# xen_daisy_motherboard_8cv8pt_mki.net
KiCad netlist of a schematic drawn in EAGLE
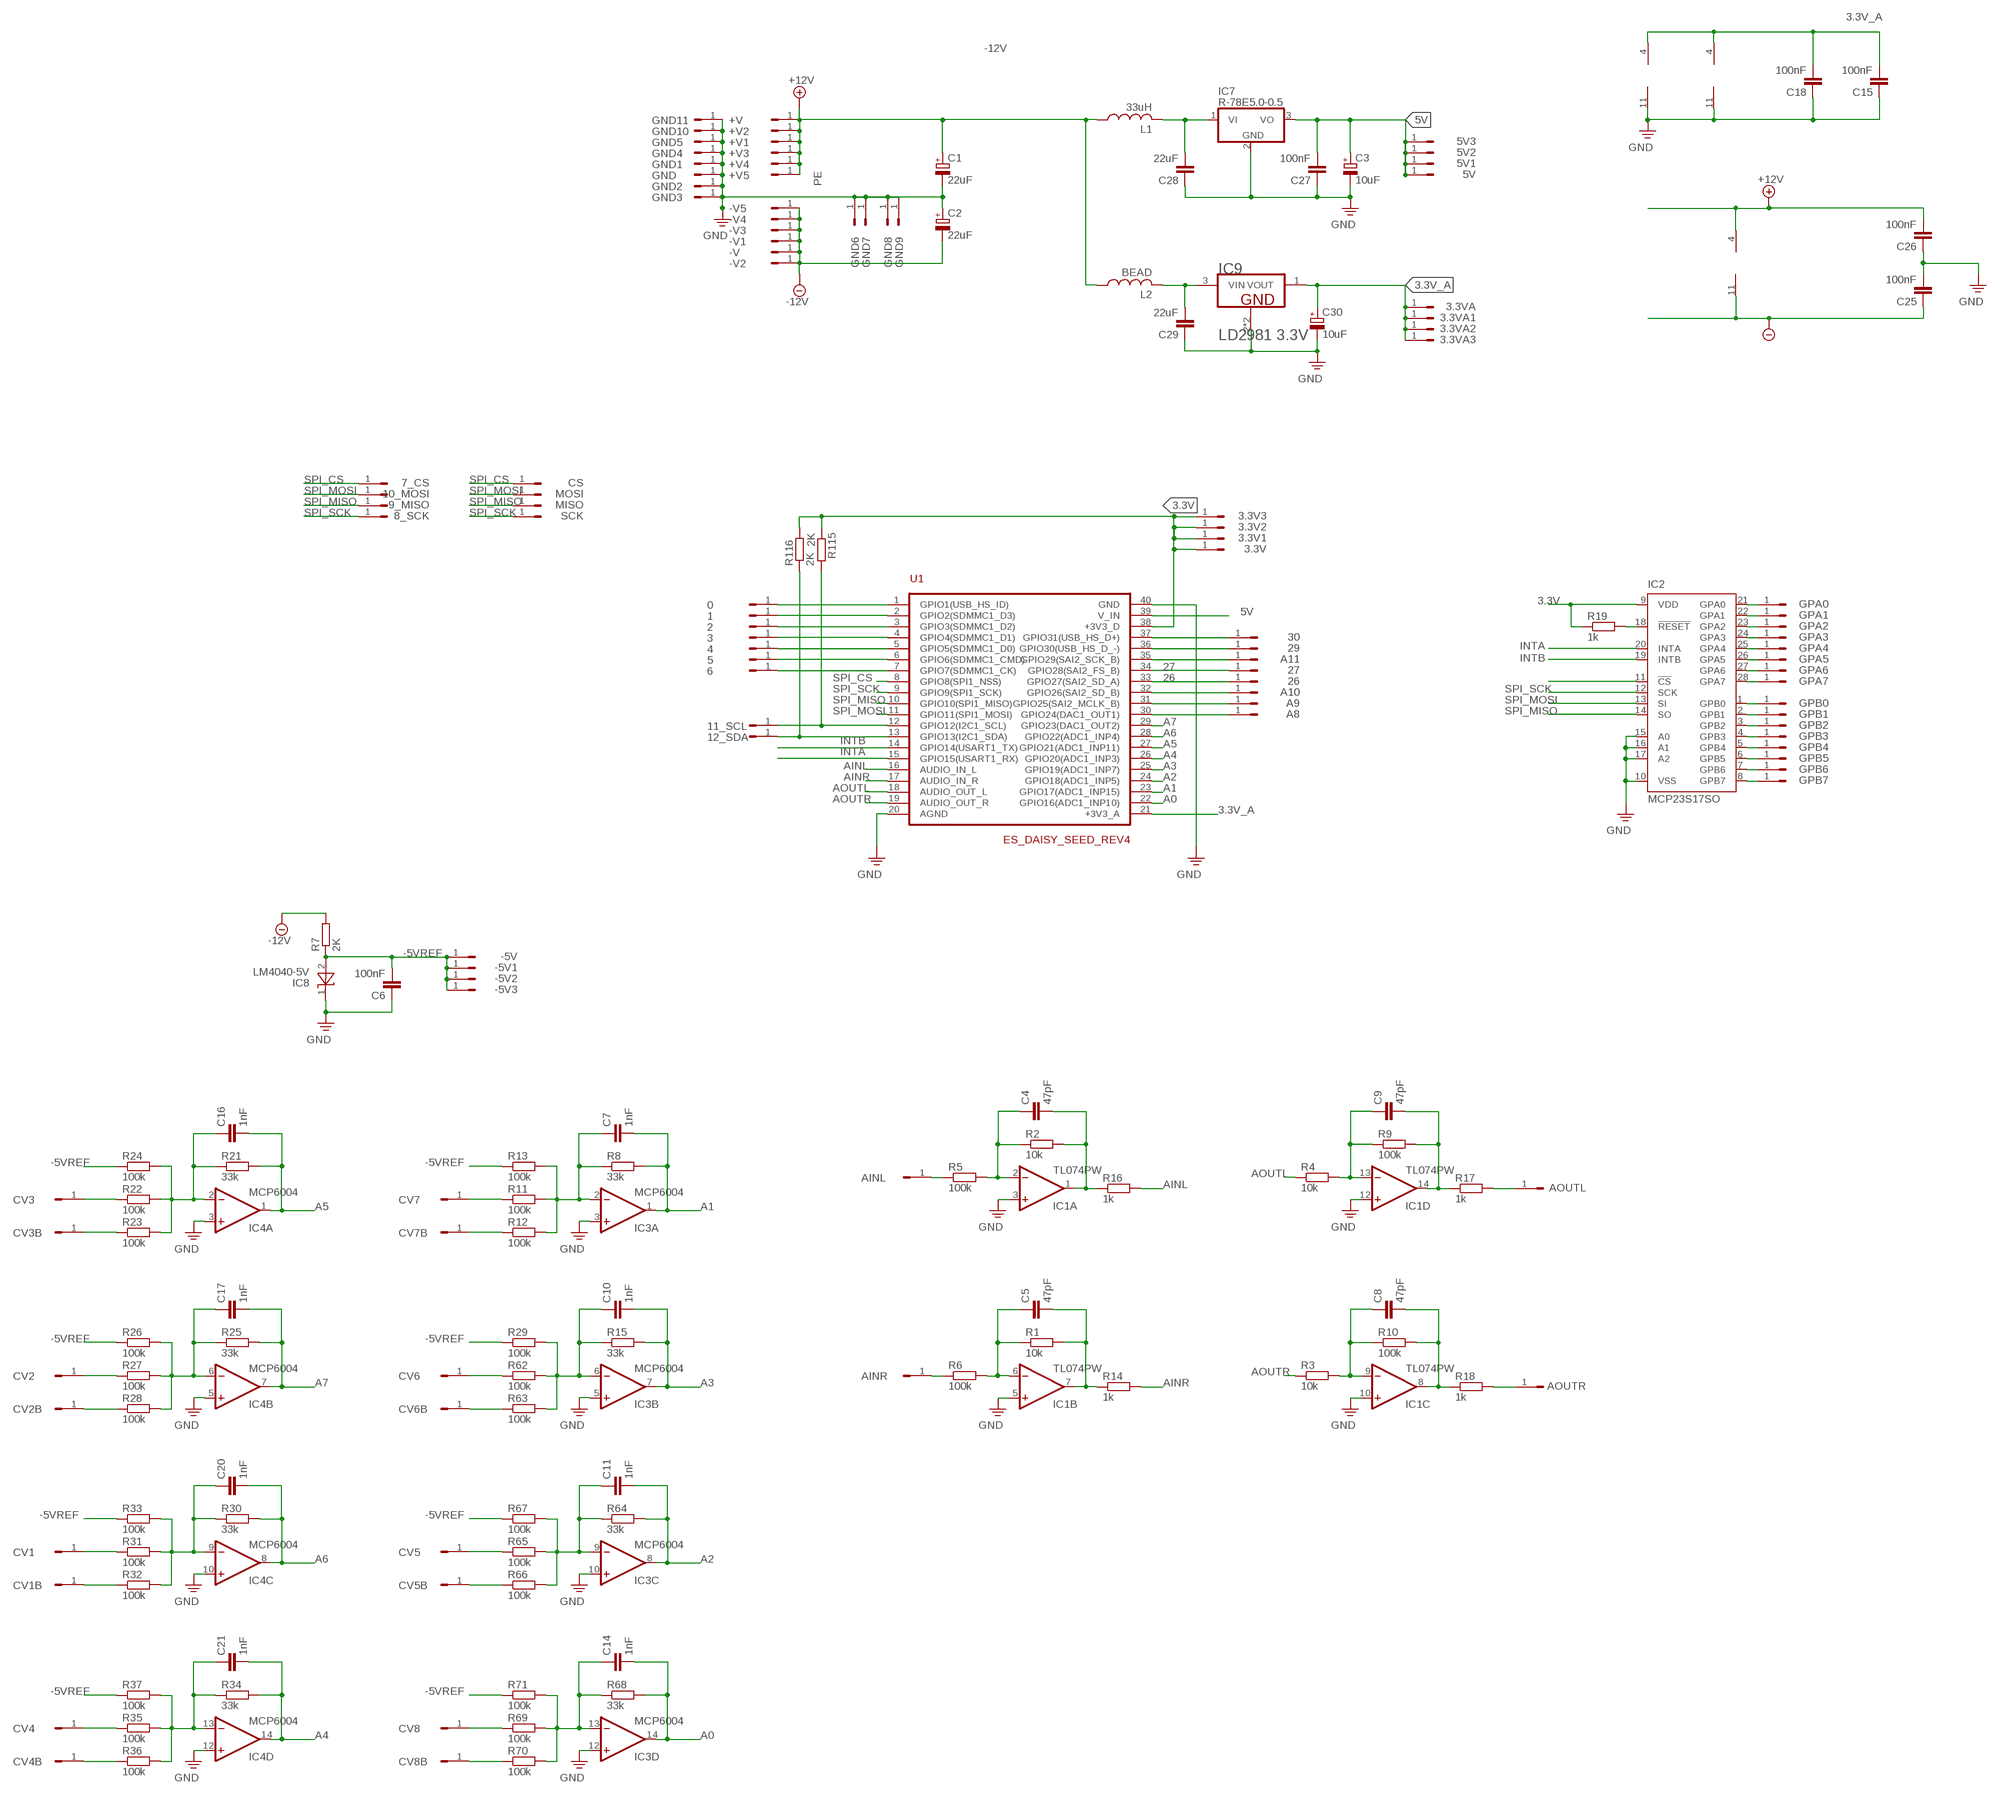
[diagram p0: schematic, sheet 1]

(export (version "E")
  (design (tool "Eeschema 10.0.6"))
  (components
    (comp (ref "+V")
      (value "HEADER/MALE/01")
      (footprint "eagle-import:HEADER_MALE_01")
      (fields (field (name "SPICEPREFIX") "X"))
      (libsource (lib "eagle-import") (part "HEADER/MALE/01"))
    )
    (comp (ref "+V1")
      (value "HEADER/MALE/01")
      (footprint "eagle-import:HEADER_MALE_01")
      (fields (field (name "SPICEPREFIX") "X"))
      (libsource (lib "eagle-import") (part "HEADER/MALE/01"))
    )
    (comp (ref "+V2")
      (value "HEADER/MALE/01")
      (footprint "eagle-import:HEADER_MALE_01")
      (fields (field (name "SPICEPREFIX") "X"))
      (libsource (lib "eagle-import") (part "HEADER/MALE/01"))
    )
    (comp (ref "+V3")
      (value "HEADER/MALE/01")
      (footprint "eagle-import:HEADER_MALE_01")
      (fields (field (name "SPICEPREFIX") "X"))
      (libsource (lib "eagle-import") (part "HEADER/MALE/01"))
    )
    (comp (ref "+V4")
      (value "HEADER/MALE/01")
      (footprint "eagle-import:HEADER_MALE_01")
      (fields (field (name "SPICEPREFIX") "X"))
      (libsource (lib "eagle-import") (part "HEADER/MALE/01"))
    )
    (comp (ref "+V5")
      (value "HEADER/MALE/01")
      (footprint "eagle-import:HEADER_MALE_01")
      (fields (field (name "SPICEPREFIX") "X"))
      (libsource (lib "eagle-import") (part "HEADER/MALE/01"))
    )
    (comp (ref "-5V")
      (value "HEADER/MALE/01")
      (footprint "eagle-import:HEADER_MALE_01")
      (fields (field (name "SPICEPREFIX") "X"))
      (libsource (lib "eagle-import") (part "HEADER/MALE/01"))
    )
    (comp (ref "-5V1")
      (value "HEADER/MALE/01")
      (footprint "eagle-import:HEADER_MALE_01")
      (fields (field (name "SPICEPREFIX") "X"))
      (libsource (lib "eagle-import") (part "HEADER/MALE/01"))
    )
    (comp (ref "-5V2")
      (value "HEADER/MALE/01")
      (footprint "eagle-import:HEADER_MALE_01")
      (fields (field (name "SPICEPREFIX") "X"))
      (libsource (lib "eagle-import") (part "HEADER/MALE/01"))
    )
    (comp (ref "-5V3")
      (value "HEADER/MALE/01")
      (footprint "eagle-import:HEADER_MALE_01")
      (fields (field (name "SPICEPREFIX") "X"))
      (libsource (lib "eagle-import") (part "HEADER/MALE/01"))
    )
    (comp (ref "-V")
      (value "HEADER/MALE/01")
      (footprint "eagle-import:HEADER_MALE_01")
      (fields (field (name "SPICEPREFIX") "X"))
      (libsource (lib "eagle-import") (part "HEADER/MALE/01"))
    )
    (comp (ref "-V1")
      (value "HEADER/MALE/01")
      (footprint "eagle-import:HEADER_MALE_01")
      (fields (field (name "SPICEPREFIX") "X"))
      (libsource (lib "eagle-import") (part "HEADER/MALE/01"))
    )
    (comp (ref "-V2")
      (value "HEADER/MALE/01")
      (footprint "eagle-import:HEADER_MALE_01")
      (fields (field (name "SPICEPREFIX") "X"))
      (libsource (lib "eagle-import") (part "HEADER/MALE/01"))
    )
    (comp (ref "-V3")
      (value "HEADER/MALE/01")
      (footprint "eagle-import:HEADER_MALE_01")
      (fields (field (name "SPICEPREFIX") "X"))
      (libsource (lib "eagle-import") (part "HEADER/MALE/01"))
    )
    (comp (ref "-V4")
      (value "HEADER/MALE/01")
      (footprint "eagle-import:HEADER_MALE_01")
      (fields (field (name "SPICEPREFIX") "X"))
      (libsource (lib "eagle-import") (part "HEADER/MALE/01"))
    )
    (comp (ref "-V5")
      (value "HEADER/MALE/01")
      (footprint "eagle-import:HEADER_MALE_01")
      (fields (field (name "SPICEPREFIX") "X"))
      (libsource (lib "eagle-import") (part "HEADER/MALE/01"))
    )
    (comp (ref "0")
      (value "HEADER/MALE/01")
      (footprint "eagle-import:HEADER_MALE_01")
      (fields (field (name "SPICEPREFIX") "X"))
      (libsource (lib "eagle-import") (part "HEADER/MALE/01"))
    )
    (comp (ref "1")
      (value "HEADER/MALE/01")
      (footprint "eagle-import:HEADER_MALE_01")
      (fields (field (name "SPICEPREFIX") "X"))
      (libsource (lib "eagle-import") (part "HEADER/MALE/01"))
    )
    (comp (ref "2")
      (value "HEADER/MALE/01")
      (footprint "eagle-import:HEADER_MALE_01")
      (fields (field (name "SPICEPREFIX") "X"))
      (libsource (lib "eagle-import") (part "HEADER/MALE/01"))
    )
    (comp (ref "3")
      (value "HEADER/MALE/01")
      (footprint "eagle-import:HEADER_MALE_01")
      (fields (field (name "SPICEPREFIX") "X"))
      (libsource (lib "eagle-import") (part "HEADER/MALE/01"))
    )
    (comp (ref "3.3V")
      (value "HEADER/MALE/01")
      (footprint "eagle-import:HEADER_MALE_01")
      (fields (field (name "SPICEPREFIX") "X"))
      (libsource (lib "eagle-import") (part "HEADER/MALE/01"))
    )
    (comp (ref "3.3V1")
      (value "HEADER/MALE/01")
      (footprint "eagle-import:HEADER_MALE_01")
      (fields (field (name "SPICEPREFIX") "X"))
      (libsource (lib "eagle-import") (part "HEADER/MALE/01"))
    )
    (comp (ref "3.3V2")
      (value "HEADER/MALE/01")
      (footprint "eagle-import:HEADER_MALE_01")
      (fields (field (name "SPICEPREFIX") "X"))
      (libsource (lib "eagle-import") (part "HEADER/MALE/01"))
    )
    (comp (ref "3.3V3")
      (value "HEADER/MALE/01")
      (footprint "eagle-import:HEADER_MALE_01")
      (fields (field (name "SPICEPREFIX") "X"))
      (libsource (lib "eagle-import") (part "HEADER/MALE/01"))
    )
    (comp (ref "3.3VA")
      (value "HEADER/MALE/01")
      (footprint "eagle-import:HEADER_MALE_01")
      (fields (field (name "SPICEPREFIX") "X"))
      (libsource (lib "eagle-import") (part "HEADER/MALE/01"))
    )
    (comp (ref "3.3VA1")
      (value "HEADER/MALE/01")
      (footprint "eagle-import:HEADER_MALE_01")
      (fields (field (name "SPICEPREFIX") "X"))
      (libsource (lib "eagle-import") (part "HEADER/MALE/01"))
    )
    (comp (ref "3.3VA2")
      (value "HEADER/MALE/01")
      (footprint "eagle-import:HEADER_MALE_01")
      (fields (field (name "SPICEPREFIX") "X"))
      (libsource (lib "eagle-import") (part "HEADER/MALE/01"))
    )
    (comp (ref "3.3VA3")
      (value "HEADER/MALE/01")
      (footprint "eagle-import:HEADER_MALE_01")
      (fields (field (name "SPICEPREFIX") "X"))
      (libsource (lib "eagle-import") (part "HEADER/MALE/01"))
    )
    (comp (ref "4")
      (value "HEADER/MALE/01")
      (footprint "eagle-import:HEADER_MALE_01")
      (fields (field (name "SPICEPREFIX") "X"))
      (libsource (lib "eagle-import") (part "HEADER/MALE/01"))
    )
    (comp (ref "5")
      (value "HEADER/MALE/01")
      (footprint "eagle-import:HEADER_MALE_01")
      (fields (field (name "SPICEPREFIX") "X"))
      (libsource (lib "eagle-import") (part "HEADER/MALE/01"))
    )
    (comp (ref "5V")
      (value "HEADER/MALE/01")
      (footprint "eagle-import:HEADER_MALE_01")
      (fields (field (name "SPICEPREFIX") "X"))
      (libsource (lib "eagle-import") (part "HEADER/MALE/01"))
    )
    (comp (ref "5V1")
      (value "HEADER/MALE/01")
      (footprint "eagle-import:HEADER_MALE_01")
      (fields (field (name "SPICEPREFIX") "X"))
      (libsource (lib "eagle-import") (part "HEADER/MALE/01"))
    )
    (comp (ref "5V2")
      (value "HEADER/MALE/01")
      (footprint "eagle-import:HEADER_MALE_01")
      (fields (field (name "SPICEPREFIX") "X"))
      (libsource (lib "eagle-import") (part "HEADER/MALE/01"))
    )
    (comp (ref "5V3")
      (value "HEADER/MALE/01")
      (footprint "eagle-import:HEADER_MALE_01")
      (fields (field (name "SPICEPREFIX") "X"))
      (libsource (lib "eagle-import") (part "HEADER/MALE/01"))
    )
    (comp (ref "6")
      (value "HEADER/MALE/01")
      (footprint "eagle-import:HEADER_MALE_01")
      (fields (field (name "SPICEPREFIX") "X"))
      (libsource (lib "eagle-import") (part "HEADER/MALE/01"))
    )
    (comp (ref "7_CS")
      (value "HEADER/MALE/01")
      (footprint "eagle-import:HEADER_MALE_01")
      (fields (field (name "SPICEPREFIX") "X"))
      (libsource (lib "eagle-import") (part "HEADER/MALE/01"))
    )
    (comp (ref "8_SCK")
      (value "HEADER/MALE/01")
      (footprint "eagle-import:HEADER_MALE_01")
      (fields (field (name "SPICEPREFIX") "X"))
      (libsource (lib "eagle-import") (part "HEADER/MALE/01"))
    )
    (comp (ref "9_MISO")
      (value "HEADER/MALE/01")
      (footprint "eagle-import:HEADER_MALE_01")
      (fields (field (name "SPICEPREFIX") "X"))
      (libsource (lib "eagle-import") (part "HEADER/MALE/01"))
    )
    (comp (ref "10_MOSI")
      (value "HEADER/MALE/01")
      (footprint "eagle-import:HEADER_MALE_01")
      (fields (field (name "SPICEPREFIX") "X"))
      (libsource (lib "eagle-import") (part "HEADER/MALE/01"))
    )
    (comp (ref "11_SCL")
      (value "HEADER/MALE/01")
      (footprint "eagle-import:HEADER_MALE_01")
      (fields (field (name "SPICEPREFIX") "X"))
      (libsource (lib "eagle-import") (part "HEADER/MALE/01"))
    )
    (comp (ref "12_SDA")
      (value "HEADER/MALE/01")
      (footprint "eagle-import:HEADER_MALE_01")
      (fields (field (name "SPICEPREFIX") "X"))
      (libsource (lib "eagle-import") (part "HEADER/MALE/01"))
    )
    (comp (ref "26")
      (value "HEADER/MALE/01")
      (footprint "eagle-import:HEADER_MALE_01")
      (fields (field (name "SPICEPREFIX") "X"))
      (libsource (lib "eagle-import") (part "HEADER/MALE/01"))
    )
    (comp (ref "27")
      (value "HEADER/MALE/01")
      (footprint "eagle-import:HEADER_MALE_01")
      (fields (field (name "SPICEPREFIX") "X"))
      (libsource (lib "eagle-import") (part "HEADER/MALE/01"))
    )
    (comp (ref "29")
      (value "HEADER/MALE/01")
      (footprint "eagle-import:HEADER_MALE_01")
      (fields (field (name "SPICEPREFIX") "X"))
      (libsource (lib "eagle-import") (part "HEADER/MALE/01"))
    )
    (comp (ref "30")
      (value "HEADER/MALE/01")
      (footprint "eagle-import:HEADER_MALE_01")
      (fields (field (name "SPICEPREFIX") "X"))
      (libsource (lib "eagle-import") (part "HEADER/MALE/01"))
    )
    (comp (ref "A8")
      (value "HEADER/MALE/01")
      (footprint "eagle-import:HEADER_MALE_01")
      (fields (field (name "SPICEPREFIX") "X"))
      (libsource (lib "eagle-import") (part "HEADER/MALE/01"))
    )
    (comp (ref "A9")
      (value "HEADER/MALE/01")
      (footprint "eagle-import:HEADER_MALE_01")
      (fields (field (name "SPICEPREFIX") "X"))
      (libsource (lib "eagle-import") (part "HEADER/MALE/01"))
    )
    (comp (ref "A10")
      (value "HEADER/MALE/01")
      (footprint "eagle-import:HEADER_MALE_01")
      (fields (field (name "SPICEPREFIX") "X"))
      (libsource (lib "eagle-import") (part "HEADER/MALE/01"))
    )
    (comp (ref "A11")
      (value "HEADER/MALE/01")
      (footprint "eagle-import:HEADER_MALE_01")
      (fields (field (name "SPICEPREFIX") "X"))
      (libsource (lib "eagle-import") (part "HEADER/MALE/01"))
    )
    (comp (ref "AINL")
      (value "HEADER/MALE/01")
      (footprint "eagle-import:HEADER_MALE_01")
      (fields (field (name "SPICEPREFIX") "X"))
      (libsource (lib "eagle-import") (part "HEADER/MALE/01"))
    )
    (comp (ref "AINR")
      (value "HEADER/MALE/01")
      (footprint "eagle-import:HEADER_MALE_01")
      (fields (field (name "SPICEPREFIX") "X"))
      (libsource (lib "eagle-import") (part "HEADER/MALE/01"))
    )
    (comp (ref "AOUTL")
      (value "HEADER/MALE/01")
      (footprint "eagle-import:HEADER_MALE_01")
      (fields (field (name "SPICEPREFIX") "X"))
      (libsource (lib "eagle-import") (part "HEADER/MALE/01"))
    )
    (comp (ref "AOUTR")
      (value "HEADER/MALE/01")
      (footprint "eagle-import:HEADER_MALE_01")
      (fields (field (name "SPICEPREFIX") "X"))
      (libsource (lib "eagle-import") (part "HEADER/MALE/01"))
    )
    (comp (ref "C1")
      (value "22uF")
      (footprint "eagle-import:SV-C")
      (fields (field (name "SPICEPREFIX") "C"))
      (libsource (lib "eagle-import") (part "CAPACITOR/POLARIZEDSMDC"))
    )
    (comp (ref "C2")
      (value "22uF")
      (footprint "eagle-import:SV-C")
      (fields (field (name "SPICEPREFIX") "C"))
      (libsource (lib "eagle-import") (part "CAPACITOR/POLARIZEDSMDC"))
    )
    (comp (ref "C3")
      (value "10uF")
      (footprint "eagle-import:SV-B")
      (fields (field (name "SPICEPREFIX") "C"))
      (libsource (lib "eagle-import") (part "CAPACITOR/POLARIZEDSMDB"))
    )
    (comp (ref "C4")
      (value "47pF")
      (footprint "eagle-import:C0603")
      (libsource (lib "eagle-import") (part "CAPACITORC0603"))
    )
    (comp (ref "C5")
      (value "47pF")
      (footprint "eagle-import:C0603")
      (libsource (lib "eagle-import") (part "CAPACITORC0603"))
    )
    (comp (ref "C6")
      (value "100nF")
      (footprint "eagle-import:C0603")
      (libsource (lib "eagle-import") (part "CAPACITORC0603"))
    )
    (comp (ref "C7")
      (value "1nF")
      (footprint "eagle-import:C0603")
      (libsource (lib "eagle-import") (part "CAPACITORC0603"))
    )
    (comp (ref "C8")
      (value "47pF")
      (footprint "eagle-import:C0603")
      (libsource (lib "eagle-import") (part "CAPACITORC0603"))
    )
    (comp (ref "C9")
      (value "47pF")
      (footprint "eagle-import:C0603")
      (libsource (lib "eagle-import") (part "CAPACITORC0603"))
    )
    (comp (ref "C10")
      (value "1nF")
      (footprint "eagle-import:C0603")
      (libsource (lib "eagle-import") (part "CAPACITORC0603"))
    )
    (comp (ref "C11")
      (value "1nF")
      (footprint "eagle-import:C0603")
      (libsource (lib "eagle-import") (part "CAPACITORC0603"))
    )
    (comp (ref "C14")
      (value "1nF")
      (footprint "eagle-import:C0603")
      (libsource (lib "eagle-import") (part "CAPACITORC0603"))
    )
    (comp (ref "C15")
      (value "100nF")
      (footprint "eagle-import:C0603")
      (fields (field (name "SPICEPREFIX") "C"))
      (libsource (lib "eagle-import") (part "CAPACITORC0603"))
    )
    (comp (ref "C16")
      (value "1nF")
      (footprint "eagle-import:C0603")
      (libsource (lib "eagle-import") (part "CAPACITORC0603"))
    )
    (comp (ref "C17")
      (value "1nF")
      (footprint "eagle-import:C0603")
      (libsource (lib "eagle-import") (part "CAPACITORC0603"))
    )
    (comp (ref "C18")
      (value "100nF")
      (footprint "eagle-import:C0603")
      (fields (field (name "SPICEPREFIX") "C"))
      (libsource (lib "eagle-import") (part "CAPACITORC0603"))
    )
    (comp (ref "C20")
      (value "1nF")
      (footprint "eagle-import:C0603")
      (libsource (lib "eagle-import") (part "CAPACITORC0603"))
    )
    (comp (ref "C21")
      (value "1nF")
      (footprint "eagle-import:C0603")
      (libsource (lib "eagle-import") (part "CAPACITORC0603"))
    )
    (comp (ref "C25")
      (value "100nF")
      (footprint "eagle-import:C0603")
      (fields (field (name "SPICEPREFIX") "C"))
      (libsource (lib "eagle-import") (part "CAPACITORC0603"))
    )
    (comp (ref "C26")
      (value "100nF")
      (footprint "eagle-import:C0603")
      (fields (field (name "SPICEPREFIX") "C"))
      (libsource (lib "eagle-import") (part "CAPACITORC0603"))
    )
    (comp (ref "C27")
      (value "100nF")
      (footprint "eagle-import:C0603")
      (libsource (lib "eagle-import") (part "CAPACITORC0603"))
    )
    (comp (ref "C28")
      (value "22uF")
      (footprint "eagle-import:C0805")
      (libsource (lib "eagle-import") (part "CAPACITORC0805"))
    )
    (comp (ref "C29")
      (value "22uF")
      (footprint "eagle-import:C0805")
      (libsource (lib "eagle-import") (part "CAPACITORC0805"))
    )
    (comp (ref "C30")
      (value "10uF")
      (footprint "eagle-import:SV-B")
      (fields (field (name "SPICEPREFIX") "C"))
      (libsource (lib "eagle-import") (part "CAPACITOR/POLARIZEDSMDB"))
    )
    (comp (ref "CS")
      (value "HEADER/MALE/01")
      (footprint "eagle-import:HEADER_MALE_01")
      (fields (field (name "SPICEPREFIX") "X"))
      (libsource (lib "eagle-import") (part "HEADER/MALE/01"))
    )
    (comp (ref "CV1")
      (value "HEADER/MALE/01")
      (footprint "eagle-import:HEADER_MALE_01")
      (fields (field (name "SPICEPREFIX") "X"))
      (libsource (lib "eagle-import") (part "HEADER/MALE/01"))
    )
    (comp (ref "CV1B")
      (value "HEADER/MALE/01")
      (footprint "eagle-import:HEADER_MALE_01")
      (fields (field (name "SPICEPREFIX") "X"))
      (libsource (lib "eagle-import") (part "HEADER/MALE/01"))
    )
    (comp (ref "CV2")
      (value "HEADER/MALE/01")
      (footprint "eagle-import:HEADER_MALE_01")
      (fields (field (name "SPICEPREFIX") "X"))
      (libsource (lib "eagle-import") (part "HEADER/MALE/01"))
    )
    (comp (ref "CV2B")
      (value "HEADER/MALE/01")
      (footprint "eagle-import:HEADER_MALE_01")
      (fields (field (name "SPICEPREFIX") "X"))
      (libsource (lib "eagle-import") (part "HEADER/MALE/01"))
    )
    (comp (ref "CV3")
      (value "HEADER/MALE/01")
      (footprint "eagle-import:HEADER_MALE_01")
      (fields (field (name "SPICEPREFIX") "X"))
      (libsource (lib "eagle-import") (part "HEADER/MALE/01"))
    )
    (comp (ref "CV3B")
      (value "HEADER/MALE/01")
      (footprint "eagle-import:HEADER_MALE_01")
      (fields (field (name "SPICEPREFIX") "X"))
      (libsource (lib "eagle-import") (part "HEADER/MALE/01"))
    )
    (comp (ref "CV4")
      (value "HEADER/MALE/01")
      (footprint "eagle-import:HEADER_MALE_01")
      (fields (field (name "SPICEPREFIX") "X"))
      (libsource (lib "eagle-import") (part "HEADER/MALE/01"))
    )
    (comp (ref "CV4B")
      (value "HEADER/MALE/01")
      (footprint "eagle-import:HEADER_MALE_01")
      (fields (field (name "SPICEPREFIX") "X"))
      (libsource (lib "eagle-import") (part "HEADER/MALE/01"))
    )
    (comp (ref "CV5")
      (value "HEADER/MALE/01")
      (footprint "eagle-import:HEADER_MALE_01")
      (fields (field (name "SPICEPREFIX") "X"))
      (libsource (lib "eagle-import") (part "HEADER/MALE/01"))
    )
    (comp (ref "CV5B")
      (value "HEADER/MALE/01")
      (footprint "eagle-import:HEADER_MALE_01")
      (fields (field (name "SPICEPREFIX") "X"))
      (libsource (lib "eagle-import") (part "HEADER/MALE/01"))
    )
    (comp (ref "CV6")
      (value "HEADER/MALE/01")
      (footprint "eagle-import:HEADER_MALE_01")
      (fields (field (name "SPICEPREFIX") "X"))
      (libsource (lib "eagle-import") (part "HEADER/MALE/01"))
    )
    (comp (ref "CV6B")
      (value "HEADER/MALE/01")
      (footprint "eagle-import:HEADER_MALE_01")
      (fields (field (name "SPICEPREFIX") "X"))
      (libsource (lib "eagle-import") (part "HEADER/MALE/01"))
    )
    (comp (ref "CV7")
      (value "HEADER/MALE/01")
      (footprint "eagle-import:HEADER_MALE_01")
      (fields (field (name "SPICEPREFIX") "X"))
      (libsource (lib "eagle-import") (part "HEADER/MALE/01"))
    )
    (comp (ref "CV7B")
      (value "HEADER/MALE/01")
      (footprint "eagle-import:HEADER_MALE_01")
      (fields (field (name "SPICEPREFIX") "X"))
      (libsource (lib "eagle-import") (part "HEADER/MALE/01"))
    )
    (comp (ref "CV8")
      (value "HEADER/MALE/01")
      (footprint "eagle-import:HEADER_MALE_01")
      (fields (field (name "SPICEPREFIX") "X"))
      (libsource (lib "eagle-import") (part "HEADER/MALE/01"))
    )
    (comp (ref "CV8B")
      (value "HEADER/MALE/01")
      (footprint "eagle-import:HEADER_MALE_01")
      (fields (field (name "SPICEPREFIX") "X"))
      (libsource (lib "eagle-import") (part "HEADER/MALE/01"))
    )
    (comp (ref "GND")
      (value "HEADER/MALE/01")
      (footprint "eagle-import:HEADER_MALE_01")
      (fields (field (name "SPICEPREFIX") "X"))
      (libsource (lib "eagle-import") (part "HEADER/MALE/01"))
    )
    (comp (ref "GND1")
      (value "HEADER/MALE/01")
      (footprint "eagle-import:HEADER_MALE_01")
      (fields (field (name "SPICEPREFIX") "X"))
      (libsource (lib "eagle-import") (part "HEADER/MALE/01"))
    )
    (comp (ref "GND2")
      (value "HEADER/MALE/01")
      (footprint "eagle-import:HEADER_MALE_01")
      (fields (field (name "SPICEPREFIX") "X"))
      (libsource (lib "eagle-import") (part "HEADER/MALE/01"))
    )
    (comp (ref "GND3")
      (value "HEADER/MALE/01")
      (footprint "eagle-import:HEADER_MALE_01")
      (fields (field (name "SPICEPREFIX") "X"))
      (libsource (lib "eagle-import") (part "HEADER/MALE/01"))
    )
    (comp (ref "GND4")
      (value "HEADER/MALE/01")
      (footprint "eagle-import:HEADER_MALE_01")
      (fields (field (name "SPICEPREFIX") "X"))
      (libsource (lib "eagle-import") (part "HEADER/MALE/01"))
    )
    (comp (ref "GND5")
      (value "HEADER/MALE/01")
      (footprint "eagle-import:HEADER_MALE_01")
      (fields (field (name "SPICEPREFIX") "X"))
      (libsource (lib "eagle-import") (part "HEADER/MALE/01"))
    )
    (comp (ref "GND6")
      (value "HEADER/MALE/01")
      (footprint "eagle-import:HEADER_MALE_01")
      (fields (field (name "SPICEPREFIX") "X"))
      (libsource (lib "eagle-import") (part "HEADER/MALE/01"))
    )
    (comp (ref "GND7")
      (value "HEADER/MALE/01")
      (footprint "eagle-import:HEADER_MALE_01")
      (fields (field (name "SPICEPREFIX") "X"))
      (libsource (lib "eagle-import") (part "HEADER/MALE/01"))
    )
    (comp (ref "GND8")
      (value "HEADER/MALE/01")
      (footprint "eagle-import:HEADER_MALE_01")
      (fields (field (name "SPICEPREFIX") "X"))
      (libsource (lib "eagle-import") (part "HEADER/MALE/01"))
    )
    (comp (ref "GND9")
      (value "HEADER/MALE/01")
      (footprint "eagle-import:HEADER_MALE_01")
      (fields (field (name "SPICEPREFIX") "X"))
      (libsource (lib "eagle-import") (part "HEADER/MALE/01"))
    )
    (comp (ref "GND10")
      (value "HEADER/MALE/01")
      (footprint "eagle-import:HEADER_MALE_01")
      (fields (field (name "SPICEPREFIX") "X"))
      (libsource (lib "eagle-import") (part "HEADER/MALE/01"))
    )
    (comp (ref "GND11")
      (value "HEADER/MALE/01")
      (footprint "eagle-import:HEADER_MALE_01")
      (fields (field (name "SPICEPREFIX") "X"))
      (libsource (lib "eagle-import") (part "HEADER/MALE/01"))
    )
    (comp (ref "GPA0")
      (value "HEADER/MALE/01")
      (footprint "eagle-import:HEADER_MALE_01")
      (fields (field (name "SPICEPREFIX") "X"))
      (libsource (lib "eagle-import") (part "HEADER/MALE/01"))
    )
    (comp (ref "GPA1")
      (value "HEADER/MALE/01")
      (footprint "eagle-import:HEADER_MALE_01")
      (fields (field (name "SPICEPREFIX") "X"))
      (libsource (lib "eagle-import") (part "HEADER/MALE/01"))
    )
    (comp (ref "GPA2")
      (value "HEADER/MALE/01")
      (footprint "eagle-import:HEADER_MALE_01")
      (fields (field (name "SPICEPREFIX") "X"))
      (libsource (lib "eagle-import") (part "HEADER/MALE/01"))
    )
    (comp (ref "GPA3")
      (value "HEADER/MALE/01")
      (footprint "eagle-import:HEADER_MALE_01")
      (fields (field (name "SPICEPREFIX") "X"))
      (libsource (lib "eagle-import") (part "HEADER/MALE/01"))
    )
    (comp (ref "GPA4")
      (value "HEADER/MALE/01")
      (footprint "eagle-import:HEADER_MALE_01")
      (fields (field (name "SPICEPREFIX") "X"))
      (libsource (lib "eagle-import") (part "HEADER/MALE/01"))
    )
    (comp (ref "GPA5")
      (value "HEADER/MALE/01")
      (footprint "eagle-import:HEADER_MALE_01")
      (fields (field (name "SPICEPREFIX") "X"))
      (libsource (lib "eagle-import") (part "HEADER/MALE/01"))
    )
    (comp (ref "GPA6")
      (value "HEADER/MALE/01")
      (footprint "eagle-import:HEADER_MALE_01")
      (fields (field (name "SPICEPREFIX") "X"))
      (libsource (lib "eagle-import") (part "HEADER/MALE/01"))
    )
    (comp (ref "GPA7")
      (value "HEADER/MALE/01")
      (footprint "eagle-import:HEADER_MALE_01")
      (fields (field (name "SPICEPREFIX") "X"))
      (libsource (lib "eagle-import") (part "HEADER/MALE/01"))
    )
    (comp (ref "GPB0")
      (value "HEADER/MALE/01")
      (footprint "eagle-import:HEADER_MALE_01")
      (fields (field (name "SPICEPREFIX") "X"))
      (libsource (lib "eagle-import") (part "HEADER/MALE/01"))
    )
    (comp (ref "GPB1")
      (value "HEADER/MALE/01")
      (footprint "eagle-import:HEADER_MALE_01")
      (fields (field (name "SPICEPREFIX") "X"))
      (libsource (lib "eagle-import") (part "HEADER/MALE/01"))
    )
    (comp (ref "GPB2")
      (value "HEADER/MALE/01")
      (footprint "eagle-import:HEADER_MALE_01")
      (fields (field (name "SPICEPREFIX") "X"))
      (libsource (lib "eagle-import") (part "HEADER/MALE/01"))
    )
    (comp (ref "GPB3")
      (value "HEADER/MALE/01")
      (footprint "eagle-import:HEADER_MALE_01")
      (fields (field (name "SPICEPREFIX") "X"))
      (libsource (lib "eagle-import") (part "HEADER/MALE/01"))
    )
    (comp (ref "GPB4")
      (value "HEADER/MALE/01")
      (footprint "eagle-import:HEADER_MALE_01")
      (fields (field (name "SPICEPREFIX") "X"))
      (libsource (lib "eagle-import") (part "HEADER/MALE/01"))
    )
    (comp (ref "GPB5")
      (value "HEADER/MALE/01")
      (footprint "eagle-import:HEADER_MALE_01")
      (fields (field (name "SPICEPREFIX") "X"))
      (libsource (lib "eagle-import") (part "HEADER/MALE/01"))
    )
    (comp (ref "GPB6")
      (value "HEADER/MALE/01")
      (footprint "eagle-import:HEADER_MALE_01")
      (fields (field (name "SPICEPREFIX") "X"))
      (libsource (lib "eagle-import") (part "HEADER/MALE/01"))
    )
    (comp (ref "GPB7")
      (value "HEADER/MALE/01")
      (footprint "eagle-import:HEADER_MALE_01")
      (fields (field (name "SPICEPREFIX") "X"))
      (libsource (lib "eagle-import") (part "HEADER/MALE/01"))
    )
    (comp (ref "IC1")
      (value "TL074PW")
      (footprint "eagle-import:TSSOP14")
      (fields (field (name "SPICEPREFIX") "I"))
      (libsource (lib "eagle-import") (part "TL074PW"))
    )
    (comp (ref "IC2")
      (value "MCP23S17SO")
      (footprint "eagle-import:SO28W")
      (fields (field (name "MF") "MICROCHIP") (field (name "MPN") "MCP23S17-E/SO"))
      (libsource (lib "eagle-import") (part "MCP23S17SO"))
    )
    (comp (ref "IC3")
      (value "MCP6004")
      (footprint "eagle-import:TSSOP14")
      (fields (field (name "SPICEPREFIX") "I"))
      (libsource (lib "eagle-import") (part "TL074PW"))
    )
    (comp (ref "IC4")
      (value "MCP6004")
      (footprint "eagle-import:TSSOP14")
      (fields (field (name "SPICEPREFIX") "I"))
      (libsource (lib "eagle-import") (part "TL074PW"))
    )
    (comp (ref "IC7")
      (value "R-78E5.0-0.5")
      (footprint "eagle-import:WE78")
      (libsource (lib "eagle-import") (part "WE173950378"))
    )
    (comp (ref "IC8")
      (value "LM4040-5V")
      (footprint "eagle-import:SOT-23")
      (libsource (lib "eagle-import") (part "LM4040CYM3-2.5"))
    )
    (comp (ref "IC9")
      (value "LD2981 3.3V")
      (footprint "eagle-import:LD2981-SOT89")
      (fields (field (name "MF") "STMicroelectronics") (field (name "MPN") "LD2981CU33TR"))
      (libsource (lib "eagle-import") (part "LD2981LD2981-SOT89"))
    )
    (comp (ref "L1")
      (value "33uH")
      (footprint "eagle-import:L2012C")
      (libsource (lib "eagle-import") (part "INDUCTORL2012C"))
    )
    (comp (ref "L2")
      (value "BEAD")
      (footprint "eagle-import:R0603")
      (libsource (lib "eagle-import") (part "INDUCTORL0603"))
    )
    (comp (ref "MISO")
      (value "HEADER/MALE/01")
      (footprint "eagle-import:HEADER_MALE_01")
      (fields (field (name "SPICEPREFIX") "X"))
      (libsource (lib "eagle-import") (part "HEADER/MALE/01"))
    )
    (comp (ref "MOSI")
      (value "HEADER/MALE/01")
      (footprint "eagle-import:HEADER_MALE_01")
      (fields (field (name "SPICEPREFIX") "X"))
      (libsource (lib "eagle-import") (part "HEADER/MALE/01"))
    )
    (comp (ref "R1")
      (value "10k")
      (footprint "eagle-import:R0603")
      (libsource (lib "eagle-import") (part "RESISTOR"))
    )
    (comp (ref "R2")
      (value "10k")
      (footprint "eagle-import:R0603")
      (libsource (lib "eagle-import") (part "RESISTOR"))
    )
    (comp (ref "R3")
      (value "10k")
      (footprint "eagle-import:R0603")
      (libsource (lib "eagle-import") (part "RESISTOR"))
    )
    (comp (ref "R4")
      (value "10k")
      (footprint "eagle-import:R0603")
      (libsource (lib "eagle-import") (part "RESISTOR"))
    )
    (comp (ref "R5")
      (value "100k")
      (footprint "eagle-import:R0603")
      (libsource (lib "eagle-import") (part "RESISTOR"))
    )
    (comp (ref "R6")
      (value "100k")
      (footprint "eagle-import:R0603")
      (libsource (lib "eagle-import") (part "RESISTOR"))
    )
    (comp (ref "R7")
      (value "2K")
      (footprint "eagle-import:R0603")
      (libsource (lib "eagle-import") (part "RESISTOR"))
    )
    (comp (ref "R8")
      (value "33k")
      (footprint "eagle-import:R0603")
      (libsource (lib "eagle-import") (part "RESISTOR"))
    )
    (comp (ref "R9")
      (value "100k")
      (footprint "eagle-import:R0603")
      (libsource (lib "eagle-import") (part "RESISTOR"))
    )
    (comp (ref "R10")
      (value "100k")
      (footprint "eagle-import:R0603")
      (libsource (lib "eagle-import") (part "RESISTOR"))
    )
    (comp (ref "R11")
      (value "100k")
      (footprint "eagle-import:R0603")
      (libsource (lib "eagle-import") (part "RESISTOR"))
    )
    (comp (ref "R12")
      (value "100k")
      (footprint "eagle-import:R0603")
      (libsource (lib "eagle-import") (part "RESISTOR"))
    )
    (comp (ref "R13")
      (value "100k")
      (footprint "eagle-import:R0603")
      (libsource (lib "eagle-import") (part "RESISTOR"))
    )
    (comp (ref "R14")
      (value "1k")
      (footprint "eagle-import:R0603")
      (libsource (lib "eagle-import") (part "RESISTOR"))
    )
    (comp (ref "R15")
      (value "33k")
      (footprint "eagle-import:R0603")
      (libsource (lib "eagle-import") (part "RESISTOR"))
    )
    (comp (ref "R16")
      (value "1k")
      (footprint "eagle-import:R0603")
      (libsource (lib "eagle-import") (part "RESISTOR"))
    )
    (comp (ref "R17")
      (value "1k")
      (footprint "eagle-import:R0603")
      (libsource (lib "eagle-import") (part "RESISTOR"))
    )
    (comp (ref "R18")
      (value "1k")
      (footprint "eagle-import:R0603")
      (libsource (lib "eagle-import") (part "RESISTOR"))
    )
    (comp (ref "R19")
      (value "1k")
      (footprint "eagle-import:R0603")
      (libsource (lib "eagle-import") (part "RESISTOR"))
    )
    (comp (ref "R21")
      (value "33k")
      (footprint "eagle-import:R0603")
      (libsource (lib "eagle-import") (part "RESISTOR"))
    )
    (comp (ref "R22")
      (value "100k")
      (footprint "eagle-import:R0603")
      (libsource (lib "eagle-import") (part "RESISTOR"))
    )
    (comp (ref "R23")
      (value "100k")
      (footprint "eagle-import:R0603")
      (libsource (lib "eagle-import") (part "RESISTOR"))
    )
    (comp (ref "R24")
      (value "100k")
      (footprint "eagle-import:R0603")
      (libsource (lib "eagle-import") (part "RESISTOR"))
    )
    (comp (ref "R25")
      (value "33k")
      (footprint "eagle-import:R0603")
      (libsource (lib "eagle-import") (part "RESISTOR"))
    )
    (comp (ref "R26")
      (value "100k")
      (footprint "eagle-import:R0603")
      (libsource (lib "eagle-import") (part "RESISTOR"))
    )
    (comp (ref "R27")
      (value "100k")
      (footprint "eagle-import:R0603")
      (libsource (lib "eagle-import") (part "RESISTOR"))
    )
    (comp (ref "R28")
      (value "100k")
      (footprint "eagle-import:R0603")
      (libsource (lib "eagle-import") (part "RESISTOR"))
    )
    (comp (ref "R29")
      (value "100k")
      (footprint "eagle-import:R0603")
      (libsource (lib "eagle-import") (part "RESISTOR"))
    )
    (comp (ref "R30")
      (value "33k")
      (footprint "eagle-import:R0603")
      (libsource (lib "eagle-import") (part "RESISTOR"))
    )
    (comp (ref "R31")
      (value "100k")
      (footprint "eagle-import:R0603")
      (libsource (lib "eagle-import") (part "RESISTOR"))
    )
    (comp (ref "R32")
      (value "100k")
      (footprint "eagle-import:R0603")
      (libsource (lib "eagle-import") (part "RESISTOR"))
    )
    (comp (ref "R33")
      (value "100k")
      (footprint "eagle-import:R0603")
      (libsource (lib "eagle-import") (part "RESISTOR"))
    )
    (comp (ref "R34")
      (value "33k")
      (footprint "eagle-import:R0603")
      (libsource (lib "eagle-import") (part "RESISTOR"))
    )
    (comp (ref "R35")
      (value "100k")
      (footprint "eagle-import:R0603")
      (libsource (lib "eagle-import") (part "RESISTOR"))
    )
    (comp (ref "R36")
      (value "100k")
      (footprint "eagle-import:R0603")
      (libsource (lib "eagle-import") (part "RESISTOR"))
    )
    (comp (ref "R37")
      (value "100k")
      (footprint "eagle-import:R0603")
      (libsource (lib "eagle-import") (part "RESISTOR"))
    )
    (comp (ref "R62")
      (value "100k")
      (footprint "eagle-import:R0603")
      (libsource (lib "eagle-import") (part "RESISTOR"))
    )
    (comp (ref "R63")
      (value "100k")
      (footprint "eagle-import:R0603")
      (libsource (lib "eagle-import") (part "RESISTOR"))
    )
    (comp (ref "R64")
      (value "33k")
      (footprint "eagle-import:R0603")
      (libsource (lib "eagle-import") (part "RESISTOR"))
    )
    (comp (ref "R65")
      (value "100k")
      (footprint "eagle-import:R0603")
      (libsource (lib "eagle-import") (part "RESISTOR"))
    )
    (comp (ref "R66")
      (value "100k")
      (footprint "eagle-import:R0603")
      (libsource (lib "eagle-import") (part "RESISTOR"))
    )
    (comp (ref "R67")
      (value "100k")
      (footprint "eagle-import:R0603")
      (libsource (lib "eagle-import") (part "RESISTOR"))
    )
    (comp (ref "R68")
      (value "33k")
      (footprint "eagle-import:R0603")
      (libsource (lib "eagle-import") (part "RESISTOR"))
    )
    (comp (ref "R69")
      (value "100k")
      (footprint "eagle-import:R0603")
      (libsource (lib "eagle-import") (part "RESISTOR"))
    )
    (comp (ref "R70")
      (value "100k")
      (footprint "eagle-import:R0603")
      (libsource (lib "eagle-import") (part "RESISTOR"))
    )
    (comp (ref "R71")
      (value "100k")
      (footprint "eagle-import:R0603")
      (libsource (lib "eagle-import") (part "RESISTOR"))
    )
    (comp (ref "R115")
      (value "2K")
      (footprint "eagle-import:R0603")
      (libsource (lib "eagle-import") (part "RESISTOR"))
    )
    (comp (ref "R116")
      (value "2K")
      (footprint "eagle-import:R0603")
      (libsource (lib "eagle-import") (part "RESISTOR"))
    )
    (comp (ref "SCK")
      (value "HEADER/MALE/01")
      (footprint "eagle-import:HEADER_MALE_01")
      (fields (field (name "SPICEPREFIX") "X"))
      (libsource (lib "eagle-import") (part "HEADER/MALE/01"))
    )
    (comp (ref "U1")
      (value "ES_DAISY_SEED_REV4")
      (footprint "eagle-import:ES_DAISY_SEED")
      (libsource (lib "eagle-import") (part "ES_DAISY_SEED_REV4"))
    )
  )
  (nets
    (net (code "1") (name "+12V") (class "Default")
      (node (ref "+V") (pin "1") (pinfunction "3_1") (pintype "passive"))
      (node (ref "+V1") (pin "1") (pinfunction "3_1") (pintype "passive"))
      (node (ref "+V2") (pin "1") (pinfunction "3_1") (pintype "passive"))
      (node (ref "+V3") (pin "1") (pinfunction "3_1") (pintype "passive"))
      (node (ref "+V4") (pin "1") (pinfunction "3_1") (pintype "passive"))
      (node (ref "+V5") (pin "1") (pinfunction "3_1") (pintype "passive"))
      (node (ref "C1") (pin "+") (pinfunction "+_+") (pintype "passive"))
      (node (ref "C26") (pin "2") (pinfunction "2_2") (pintype "passive"))
      (node (ref "IC1") (pin "4") (pinfunction "V+_4") (pintype "power_in"))
      (node (ref "L1") (pin "1") (pinfunction "1_1") (pintype "passive"))
      (node (ref "L2") (pin "1") (pinfunction "1_1") (pintype "passive"))
    )
    (net (code "2") (name "-12V") (class "Default")
      (node (ref "-V") (pin "1") (pinfunction "3_1") (pintype "passive"))
      (node (ref "-V1") (pin "1") (pinfunction "3_1") (pintype "passive"))
      (node (ref "-V2") (pin "1") (pinfunction "3_1") (pintype "passive"))
      (node (ref "-V3") (pin "1") (pinfunction "3_1") (pintype "passive"))
      (node (ref "-V4") (pin "1") (pinfunction "3_1") (pintype "passive"))
      (node (ref "-V5") (pin "1") (pinfunction "3_1") (pintype "passive"))
      (node (ref "C2") (pin "-") (pinfunction "-_-") (pintype "passive"))
      (node (ref "C25") (pin "1") (pinfunction "1_1") (pintype "passive"))
      (node (ref "IC1") (pin "11") (pinfunction "V-_11") (pintype "power_in"))
      (node (ref "R7") (pin "2") (pinfunction "2_2") (pintype "passive"))
    )
    (net (code "3") (name "/-5VREF") (class "Default")
      (node (ref "-5V") (pin "1") (pinfunction "3_1") (pintype "passive"))
      (node (ref "-5V1") (pin "1") (pinfunction "3_1") (pintype "passive"))
      (node (ref "-5V2") (pin "1") (pinfunction "3_1") (pintype "passive"))
      (node (ref "-5V3") (pin "1") (pinfunction "3_1") (pintype "passive"))
      (node (ref "C6") (pin "2") (pinfunction "2_2") (pintype "passive"))
      (node (ref "IC8") (pin "2") (pinfunction "A_2") (pintype "output"))
      (node (ref "R13") (pin "1") (pinfunction "1_1") (pintype "passive"))
      (node (ref "R24") (pin "1") (pinfunction "1_1") (pintype "passive"))
      (node (ref "R26") (pin "1") (pinfunction "1_1") (pintype "passive"))
      (node (ref "R29") (pin "1") (pinfunction "1_1") (pintype "passive"))
      (node (ref "R33") (pin "1") (pinfunction "1_1") (pintype "passive"))
      (node (ref "R37") (pin "1") (pinfunction "1_1") (pintype "passive"))
      (node (ref "R67") (pin "1") (pinfunction "1_1") (pintype "passive"))
      (node (ref "R7") (pin "1") (pinfunction "1_1") (pintype "passive"))
      (node (ref "R71") (pin "1") (pinfunction "1_1") (pintype "passive"))
    )
    (net (code "4") (name "/26") (class "Default")
      (node (ref "26") (pin "1") (pinfunction "3_1") (pintype "passive"))
      (node (ref "U1") (pin "33") (pinfunction "GPIO27(SAI2_SD_A)_33") (pintype "bidirectional"))
    )
    (net (code "5") (name "/27") (class "Default")
      (node (ref "27") (pin "1") (pinfunction "3_1") (pintype "passive"))
      (node (ref "U1") (pin "34") (pinfunction "GPIO28(SAI2_FS_B)_34") (pintype "bidirectional"))
    )
    (net (code "6") (name "/A0") (class "Default")
      (node (ref "C14") (pin "2") (pinfunction "2_2") (pintype "passive"))
      (node (ref "IC3") (pin "14") (pinfunction "OUT_14") (pintype "output"))
      (node (ref "R68") (pin "2") (pinfunction "2_2") (pintype "passive"))
      (node (ref "U1") (pin "22") (pinfunction "GPIO16(ADC1_INP10)_22") (pintype "bidirectional"))
    )
    (net (code "7") (name "/A1") (class "Default")
      (node (ref "C7") (pin "2") (pinfunction "2_2") (pintype "passive"))
      (node (ref "IC3") (pin "1") (pinfunction "OUT_1") (pintype "output"))
      (node (ref "R8") (pin "2") (pinfunction "2_2") (pintype "passive"))
      (node (ref "U1") (pin "23") (pinfunction "GPIO17(ADC1_INP15)_23") (pintype "bidirectional"))
    )
    (net (code "8") (name "/A2") (class "Default")
      (node (ref "C11") (pin "2") (pinfunction "2_2") (pintype "passive"))
      (node (ref "IC3") (pin "8") (pinfunction "OUT_8") (pintype "output"))
      (node (ref "R64") (pin "2") (pinfunction "2_2") (pintype "passive"))
      (node (ref "U1") (pin "24") (pinfunction "GPIO18(ADC1_INP5)_24") (pintype "bidirectional"))
    )
    (net (code "9") (name "/A3") (class "Default")
      (node (ref "C10") (pin "2") (pinfunction "2_2") (pintype "passive"))
      (node (ref "IC3") (pin "7") (pinfunction "OUT_7") (pintype "output"))
      (node (ref "R15") (pin "2") (pinfunction "2_2") (pintype "passive"))
      (node (ref "U1") (pin "25") (pinfunction "GPIO19(ADC1_INP7)_25") (pintype "bidirectional"))
    )
    (net (code "10") (name "/A4") (class "Default")
      (node (ref "C21") (pin "2") (pinfunction "2_2") (pintype "passive"))
      (node (ref "IC4") (pin "14") (pinfunction "OUT_14") (pintype "output"))
      (node (ref "R34") (pin "2") (pinfunction "2_2") (pintype "passive"))
      (node (ref "U1") (pin "26") (pinfunction "GPIO20(ADC1_INP3)_26") (pintype "bidirectional"))
    )
    (net (code "11") (name "/A5") (class "Default")
      (node (ref "C16") (pin "2") (pinfunction "2_2") (pintype "passive"))
      (node (ref "IC4") (pin "1") (pinfunction "OUT_1") (pintype "output"))
      (node (ref "R21") (pin "2") (pinfunction "2_2") (pintype "passive"))
      (node (ref "U1") (pin "27") (pinfunction "GPIO21(ADC1_INP11)_27") (pintype "bidirectional"))
    )
    (net (code "12") (name "/A6") (class "Default")
      (node (ref "C20") (pin "2") (pinfunction "2_2") (pintype "passive"))
      (node (ref "IC4") (pin "8") (pinfunction "OUT_8") (pintype "output"))
      (node (ref "R30") (pin "2") (pinfunction "2_2") (pintype "passive"))
      (node (ref "U1") (pin "28") (pinfunction "GPIO22(ADC1_INP4)_28") (pintype "bidirectional"))
    )
    (net (code "13") (name "/A7") (class "Default")
      (node (ref "C17") (pin "2") (pinfunction "2_2") (pintype "passive"))
      (node (ref "IC4") (pin "7") (pinfunction "OUT_7") (pintype "output"))
      (node (ref "R25") (pin "2") (pinfunction "2_2") (pintype "passive"))
      (node (ref "U1") (pin "29") (pinfunction "GPIO23(DAC1_OUT2)_29") (pintype "bidirectional"))
    )
    (net (code "14") (name "/AINL") (class "Default")
      (node (ref "R16") (pin "2") (pinfunction "2_2") (pintype "passive"))
      (node (ref "U1") (pin "16") (pinfunction "AUDIO_IN_L_16") (pintype "bidirectional"))
    )
    (net (code "15") (name "/AINR") (class "Default")
      (node (ref "R14") (pin "2") (pinfunction "2_2") (pintype "passive"))
      (node (ref "U1") (pin "17") (pinfunction "AUDIO_IN_R_17") (pintype "bidirectional"))
    )
    (net (code "16") (name "/AOUTL") (class "Default")
      (node (ref "R4") (pin "1") (pinfunction "1_1") (pintype "passive"))
      (node (ref "U1") (pin "18") (pinfunction "AUDIO_OUT_L_18") (pintype "bidirectional"))
    )
    (net (code "17") (name "/AOUTR") (class "Default")
      (node (ref "R3") (pin "1") (pinfunction "1_1") (pintype "passive"))
      (node (ref "U1") (pin "19") (pinfunction "AUDIO_OUT_R_19") (pintype "bidirectional"))
    )
    (net (code "18") (name "/INTA") (class "Default")
      (node (ref "IC2") (pin "20") (pinfunction "INTA_20") (pintype "output"))
      (node (ref "U1") (pin "15") (pinfunction "GPIO15(USART1_RX)_15") (pintype "bidirectional"))
    )
    (net (code "19") (name "/INTB") (class "Default")
      (node (ref "IC2") (pin "19") (pinfunction "INTB_19") (pintype "output"))
      (node (ref "U1") (pin "14") (pinfunction "GPIO14(USART1_TX)_14") (pintype "bidirectional"))
    )
    (net (code "20") (name "/SPI_CS") (class "Default")
      (node (ref "7_CS") (pin "1") (pinfunction "3_1") (pintype "passive"))
      (node (ref "CS") (pin "1") (pinfunction "3_1") (pintype "passive"))
      (node (ref "U1") (pin "8") (pinfunction "GPIO8(SPI1_NSS)_8") (pintype "bidirectional"))
    )
    (net (code "21") (name "/SPI_MISO") (class "Default")
      (node (ref "9_MISO") (pin "1") (pinfunction "3_1") (pintype "passive"))
      (node (ref "IC2") (pin "14") (pinfunction "SO_14") (pintype "output"))
      (node (ref "MISO") (pin "1") (pinfunction "3_1") (pintype "passive"))
      (node (ref "U1") (pin "10") (pinfunction "GPIO10(SPI1_MISO)_10") (pintype "bidirectional"))
    )
    (net (code "22") (name "/SPI_MOSI") (class "Default")
      (node (ref "10_MOSI") (pin "1") (pinfunction "3_1") (pintype "passive"))
      (node (ref "IC2") (pin "13") (pinfunction "SI_13") (pintype "input"))
      (node (ref "MOSI") (pin "1") (pinfunction "3_1") (pintype "passive"))
      (node (ref "U1") (pin "11") (pinfunction "GPIO11(SPI1_MOSI)_11") (pintype "bidirectional"))
    )
    (net (code "23") (name "/SPI_SCK") (class "Default")
      (node (ref "8_SCK") (pin "1") (pinfunction "3_1") (pintype "passive"))
      (node (ref "IC2") (pin "12") (pinfunction "SCK_12") (pintype "input"))
      (node (ref "SCK") (pin "1") (pinfunction "3_1") (pintype "passive"))
      (node (ref "U1") (pin "9") (pinfunction "GPIO9(SPI1_SCK)_9") (pintype "bidirectional"))
    )
    (net (code "24") (name "3.3V") (class "Default")
      (node (ref "3.3V") (pin "1") (pinfunction "3_1") (pintype "passive"))
      (node (ref "3.3V1") (pin "1") (pinfunction "3_1") (pintype "passive"))
      (node (ref "3.3V2") (pin "1") (pinfunction "3_1") (pintype "passive"))
      (node (ref "3.3V3") (pin "1") (pinfunction "3_1") (pintype "passive"))
      (node (ref "IC2") (pin "9") (pinfunction "VDD_9") (pintype "power_in"))
      (node (ref "R115") (pin "1") (pinfunction "1_1") (pintype "passive"))
      (node (ref "R116") (pin "2") (pinfunction "2_2") (pintype "passive"))
      (node (ref "R19") (pin "1") (pinfunction "1_1") (pintype "passive"))
      (node (ref "U1") (pin "38") (pinfunction "+3V3_D_38") (pintype "bidirectional"))
    )
    (net (code "25") (name "3.3V_A") (class "Default")
      (node (ref "3.3VA") (pin "1") (pinfunction "3_1") (pintype "passive"))
      (node (ref "3.3VA1") (pin "1") (pinfunction "3_1") (pintype "passive"))
      (node (ref "3.3VA2") (pin "1") (pinfunction "3_1") (pintype "passive"))
      (node (ref "3.3VA3") (pin "1") (pinfunction "3_1") (pintype "passive"))
      (node (ref "C15") (pin "2") (pinfunction "2_2") (pintype "passive"))
      (node (ref "C18") (pin "2") (pinfunction "2_2") (pintype "passive"))
      (node (ref "C30") (pin "+") (pinfunction "+_+") (pintype "passive"))
      (node (ref "IC3") (pin "4") (pinfunction "V+_4") (pintype "power_in"))
      (node (ref "IC4") (pin "4") (pinfunction "V+_4") (pintype "power_in"))
      (node (ref "IC9") (pin "1") (pinfunction "VOUT_1") (pintype "power_in"))
      (node (ref "U1") (pin "21") (pinfunction "+3V3_A_21") (pintype "bidirectional"))
    )
    (net (code "26") (name "5V") (class "Default")
      (node (ref "5V") (pin "1") (pinfunction "3_1") (pintype "passive"))
      (node (ref "5V1") (pin "1") (pinfunction "3_1") (pintype "passive"))
      (node (ref "5V2") (pin "1") (pinfunction "3_1") (pintype "passive"))
      (node (ref "5V3") (pin "1") (pinfunction "3_1") (pintype "passive"))
      (node (ref "C27") (pin "2") (pinfunction "2_2") (pintype "passive"))
      (node (ref "C3") (pin "+") (pinfunction "+_+") (pintype "passive"))
      (node (ref "IC7") (pin "3") (pinfunction "VO_3") (pintype "passive"))
      (node (ref "U1") (pin "39") (pinfunction "V_IN_39") (pintype "bidirectional"))
    )
    (net (code "27") (name "GND") (class "Default")
      (node (ref "C1") (pin "-") (pinfunction "-_-") (pintype "passive"))
      (node (ref "C15") (pin "1") (pinfunction "1_1") (pintype "passive"))
      (node (ref "C18") (pin "1") (pinfunction "1_1") (pintype "passive"))
      (node (ref "C2") (pin "+") (pinfunction "+_+") (pintype "passive"))
      (node (ref "C25") (pin "2") (pinfunction "2_2") (pintype "passive"))
      (node (ref "C26") (pin "1") (pinfunction "1_1") (pintype "passive"))
      (node (ref "C27") (pin "1") (pinfunction "1_1") (pintype "passive"))
      (node (ref "C28") (pin "1") (pinfunction "1_1") (pintype "passive"))
      (node (ref "C29") (pin "1") (pinfunction "1_1") (pintype "passive"))
      (node (ref "C3") (pin "-") (pinfunction "-_-") (pintype "passive"))
      (node (ref "C30") (pin "-") (pinfunction "-_-") (pintype "passive"))
      (node (ref "C6") (pin "1") (pinfunction "1_1") (pintype "passive"))
      (node (ref "GND") (pin "1") (pinfunction "3_1") (pintype "passive"))
      (node (ref "GND1") (pin "1") (pinfunction "3_1") (pintype "passive"))
      (node (ref "GND10") (pin "1") (pinfunction "3_1") (pintype "passive"))
      (node (ref "GND11") (pin "1") (pinfunction "3_1") (pintype "passive"))
      (node (ref "GND2") (pin "1") (pinfunction "3_1") (pintype "passive"))
      (node (ref "GND3") (pin "1") (pinfunction "3_1") (pintype "passive"))
      (node (ref "GND4") (pin "1") (pinfunction "3_1") (pintype "passive"))
      (node (ref "GND5") (pin "1") (pinfunction "3_1") (pintype "passive"))
      (node (ref "GND6") (pin "1") (pinfunction "3_1") (pintype "passive"))
      (node (ref "GND7") (pin "1") (pinfunction "3_1") (pintype "passive"))
      (node (ref "GND8") (pin "1") (pinfunction "3_1") (pintype "passive"))
      (node (ref "GND9") (pin "1") (pinfunction "3_1") (pintype "passive"))
      (node (ref "IC1") (pin "10") (pinfunction "+IN_10") (pintype "input"))
      (node (ref "IC1") (pin "12") (pinfunction "+IN_12") (pintype "input"))
      (node (ref "IC1") (pin "3") (pinfunction "+IN_3") (pintype "input"))
      (node (ref "IC1") (pin "5") (pinfunction "+IN_5") (pintype "input"))
      (node (ref "IC2") (pin "10") (pinfunction "VSS_10") (pintype "power_in"))
      (node (ref "IC2") (pin "15") (pinfunction "A0_15") (pintype "input"))
      (node (ref "IC2") (pin "16") (pinfunction "A1_16") (pintype "input"))
      (node (ref "IC2") (pin "17") (pinfunction "A2_17") (pintype "input"))
      (node (ref "IC3") (pin "10") (pinfunction "+IN_10") (pintype "input"))
      (node (ref "IC3") (pin "11") (pinfunction "V-_11") (pintype "power_in"))
      (node (ref "IC3") (pin "12") (pinfunction "+IN_12") (pintype "input"))
      (node (ref "IC3") (pin "3") (pinfunction "+IN_3") (pintype "input"))
      (node (ref "IC3") (pin "5") (pinfunction "+IN_5") (pintype "input"))
      (node (ref "IC4") (pin "10") (pinfunction "+IN_10") (pintype "input"))
      (node (ref "IC4") (pin "11") (pinfunction "V-_11") (pintype "power_in"))
      (node (ref "IC4") (pin "12") (pinfunction "+IN_12") (pintype "input"))
      (node (ref "IC4") (pin "3") (pinfunction "+IN_3") (pintype "input"))
      (node (ref "IC4") (pin "5") (pinfunction "+IN_5") (pintype "input"))
      (node (ref "IC7") (pin "2") (pinfunction "GND_2") (pintype "passive"))
      (node (ref "IC8") (pin "1") (pinfunction "C_1") (pintype "input"))
      (node (ref "IC9") (pin "2") (pinfunction "GND_2") (pintype "power_in"))
      (node (ref "IC9") (pin "2-2") (pinfunction "GND_2-2") (pintype "power_in"))
      (node (ref "U1") (pin "20") (pinfunction "AGND_20") (pintype "bidirectional"))
      (node (ref "U1") (pin "40") (pinfunction "GND_40") (pintype "bidirectional"))
    )
    (net (code "28") (name "Net-(0-3)") (class "Default")
      (node (ref "0") (pin "1") (pinfunction "3_1") (pintype "passive"))
      (node (ref "U1") (pin "1") (pinfunction "GPIO1(USB_HS_ID)_1") (pintype "bidirectional"))
    )
    (net (code "29") (name "Net-(1-3)") (class "Default")
      (node (ref "1") (pin "1") (pinfunction "3_1") (pintype "passive"))
      (node (ref "U1") (pin "2") (pinfunction "GPIO2(SDMMC1_D3)_2") (pintype "bidirectional"))
    )
    (net (code "30") (name "Net-(2-3)") (class "Default")
      (node (ref "2") (pin "1") (pinfunction "3_1") (pintype "passive"))
      (node (ref "U1") (pin "3") (pinfunction "GPIO3(SDMMC1_D2)_3") (pintype "bidirectional"))
    )
    (net (code "31") (name "Net-(3-3)") (class "Default")
      (node (ref "3") (pin "1") (pinfunction "3_1") (pintype "passive"))
      (node (ref "U1") (pin "4") (pinfunction "GPIO4(SDMMC1_D1)_4") (pintype "bidirectional"))
    )
    (net (code "32") (name "Net-(4-3)") (class "Default")
      (node (ref "4") (pin "1") (pinfunction "3_1") (pintype "passive"))
      (node (ref "U1") (pin "5") (pinfunction "GPIO5(SDMMC1_D0)_5") (pintype "bidirectional"))
    )
    (net (code "33") (name "Net-(5-3)") (class "Default")
      (node (ref "5") (pin "1") (pinfunction "3_1") (pintype "passive"))
      (node (ref "U1") (pin "6") (pinfunction "GPIO6(SDMMC1_CMD)_6") (pintype "bidirectional"))
    )
    (net (code "34") (name "Net-(6-3)") (class "Default")
      (node (ref "6") (pin "1") (pinfunction "3_1") (pintype "passive"))
      (node (ref "U1") (pin "7") (pinfunction "GPIO7(SDMMC1_CK)_7") (pintype "bidirectional"))
    )
    (net (code "35") (name "Net-(11_SCL-3)") (class "Default")
      (node (ref "11_SCL") (pin "1") (pinfunction "3_1") (pintype "passive"))
      (node (ref "R115") (pin "2") (pinfunction "2_2") (pintype "passive"))
      (node (ref "U1") (pin "12") (pinfunction "GPIO12(I2C1_SCL)_12") (pintype "bidirectional"))
    )
    (net (code "36") (name "Net-(12_SDA-3)") (class "Default")
      (node (ref "12_SDA") (pin "1") (pinfunction "3_1") (pintype "passive"))
      (node (ref "R116") (pin "1") (pinfunction "1_1") (pintype "passive"))
      (node (ref "U1") (pin "13") (pinfunction "GPIO13(I2C1_SDA)_13") (pintype "bidirectional"))
    )
    (net (code "37") (name "Net-(29-3)") (class "Default")
      (node (ref "29") (pin "1") (pinfunction "3_1") (pintype "passive"))
      (node (ref "U1") (pin "36") (pinfunction "GPIO30(USB_HS_D_-)_36") (pintype "bidirectional"))
    )
    (net (code "38") (name "Net-(30-3)") (class "Default")
      (node (ref "30") (pin "1") (pinfunction "3_1") (pintype "passive"))
      (node (ref "U1") (pin "37") (pinfunction "GPIO31(USB_HS_D+)_37") (pintype "bidirectional"))
    )
    (net (code "39") (name "Net-(A8-3)") (class "Default")
      (node (ref "A8") (pin "1") (pinfunction "3_1") (pintype "passive"))
      (node (ref "U1") (pin "30") (pinfunction "GPIO24(DAC1_OUT1)_30") (pintype "bidirectional"))
    )
    (net (code "40") (name "Net-(A9-3)") (class "Default")
      (node (ref "A9") (pin "1") (pinfunction "3_1") (pintype "passive"))
      (node (ref "U1") (pin "31") (pinfunction "GPIO25(SAI2_MCLK_B)_31") (pintype "bidirectional"))
    )
    (net (code "41") (name "Net-(A10-3)") (class "Default")
      (node (ref "A10") (pin "1") (pinfunction "3_1") (pintype "passive"))
      (node (ref "U1") (pin "32") (pinfunction "GPIO26(SAI2_SD_B)_32") (pintype "bidirectional"))
    )
    (net (code "42") (name "Net-(A11-3)") (class "Default")
      (node (ref "A11") (pin "1") (pinfunction "3_1") (pintype "passive"))
      (node (ref "U1") (pin "35") (pinfunction "GPIO29(SAI2_SCK_B)_35") (pintype "bidirectional"))
    )
    (net (code "43") (name "Net-(AINL-3)") (class "Default")
      (node (ref "AINL") (pin "1") (pinfunction "3_1") (pintype "passive"))
      (node (ref "R5") (pin "1") (pinfunction "1_1") (pintype "passive"))
    )
    (net (code "44") (name "Net-(AINR-3)") (class "Default")
      (node (ref "AINR") (pin "1") (pinfunction "3_1") (pintype "passive"))
      (node (ref "R6") (pin "1") (pinfunction "1_1") (pintype "passive"))
    )
    (net (code "45") (name "Net-(AOUTL-3)") (class "Default")
      (node (ref "AOUTL") (pin "1") (pinfunction "3_1") (pintype "passive"))
      (node (ref "R17") (pin "2") (pinfunction "2_2") (pintype "passive"))
    )
    (net (code "46") (name "Net-(AOUTR-3)") (class "Default")
      (node (ref "AOUTR") (pin "1") (pinfunction "3_1") (pintype "passive"))
      (node (ref "R18") (pin "2") (pinfunction "2_2") (pintype "passive"))
    )
    (net (code "47") (name "Net-(CV1-3)") (class "Default")
      (node (ref "CV1") (pin "1") (pinfunction "3_1") (pintype "passive"))
      (node (ref "R31") (pin "1") (pinfunction "1_1") (pintype "passive"))
    )
    (net (code "48") (name "Net-(CV1B-3)") (class "Default")
      (node (ref "CV1B") (pin "1") (pinfunction "3_1") (pintype "passive"))
      (node (ref "R32") (pin "1") (pinfunction "1_1") (pintype "passive"))
    )
    (net (code "49") (name "Net-(CV2-3)") (class "Default")
      (node (ref "CV2") (pin "1") (pinfunction "3_1") (pintype "passive"))
      (node (ref "R27") (pin "1") (pinfunction "1_1") (pintype "passive"))
    )
    (net (code "50") (name "Net-(CV2B-3)") (class "Default")
      (node (ref "CV2B") (pin "1") (pinfunction "3_1") (pintype "passive"))
      (node (ref "R28") (pin "1") (pinfunction "1_1") (pintype "passive"))
    )
    (net (code "51") (name "Net-(CV3-3)") (class "Default")
      (node (ref "CV3") (pin "1") (pinfunction "3_1") (pintype "passive"))
      (node (ref "R22") (pin "1") (pinfunction "1_1") (pintype "passive"))
    )
    (net (code "52") (name "Net-(CV3B-3)") (class "Default")
      (node (ref "CV3B") (pin "1") (pinfunction "3_1") (pintype "passive"))
      (node (ref "R23") (pin "1") (pinfunction "1_1") (pintype "passive"))
    )
    (net (code "53") (name "Net-(CV4-3)") (class "Default")
      (node (ref "CV4") (pin "1") (pinfunction "3_1") (pintype "passive"))
      (node (ref "R35") (pin "1") (pinfunction "1_1") (pintype "passive"))
    )
    (net (code "54") (name "Net-(CV4B-3)") (class "Default")
      (node (ref "CV4B") (pin "1") (pinfunction "3_1") (pintype "passive"))
      (node (ref "R36") (pin "1") (pinfunction "1_1") (pintype "passive"))
    )
    (net (code "55") (name "Net-(CV5-3)") (class "Default")
      (node (ref "CV5") (pin "1") (pinfunction "3_1") (pintype "passive"))
      (node (ref "R65") (pin "1") (pinfunction "1_1") (pintype "passive"))
    )
    (net (code "56") (name "Net-(CV5B-3)") (class "Default")
      (node (ref "CV5B") (pin "1") (pinfunction "3_1") (pintype "passive"))
      (node (ref "R66") (pin "1") (pinfunction "1_1") (pintype "passive"))
    )
    (net (code "57") (name "Net-(CV6-3)") (class "Default")
      (node (ref "CV6") (pin "1") (pinfunction "3_1") (pintype "passive"))
      (node (ref "R62") (pin "1") (pinfunction "1_1") (pintype "passive"))
    )
    (net (code "58") (name "Net-(CV6B-3)") (class "Default")
      (node (ref "CV6B") (pin "1") (pinfunction "3_1") (pintype "passive"))
      (node (ref "R63") (pin "1") (pinfunction "1_1") (pintype "passive"))
    )
    (net (code "59") (name "Net-(CV7-3)") (class "Default")
      (node (ref "CV7") (pin "1") (pinfunction "3_1") (pintype "passive"))
      (node (ref "R11") (pin "1") (pinfunction "1_1") (pintype "passive"))
    )
    (net (code "60") (name "Net-(CV7B-3)") (class "Default")
      (node (ref "CV7B") (pin "1") (pinfunction "3_1") (pintype "passive"))
      (node (ref "R12") (pin "1") (pinfunction "1_1") (pintype "passive"))
    )
    (net (code "61") (name "Net-(CV8-3)") (class "Default")
      (node (ref "CV8") (pin "1") (pinfunction "3_1") (pintype "passive"))
      (node (ref "R69") (pin "1") (pinfunction "1_1") (pintype "passive"))
    )
    (net (code "62") (name "Net-(CV8B-3)") (class "Default")
      (node (ref "CV8B") (pin "1") (pinfunction "3_1") (pintype "passive"))
      (node (ref "R70") (pin "1") (pinfunction "1_1") (pintype "passive"))
    )
    (net (code "63") (name "Net-(GPA0-3)") (class "Default")
      (node (ref "GPA0") (pin "1") (pinfunction "3_1") (pintype "passive"))
      (node (ref "IC2") (pin "21") (pinfunction "GPA0_21") (pintype "bidirectional"))
    )
    (net (code "64") (name "Net-(GPA1-3)") (class "Default")
      (node (ref "GPA1") (pin "1") (pinfunction "3_1") (pintype "passive"))
      (node (ref "IC2") (pin "22") (pinfunction "GPA1_22") (pintype "bidirectional"))
    )
    (net (code "65") (name "Net-(GPA2-3)") (class "Default")
      (node (ref "GPA2") (pin "1") (pinfunction "3_1") (pintype "passive"))
      (node (ref "IC2") (pin "23") (pinfunction "GPA2_23") (pintype "bidirectional"))
    )
    (net (code "66") (name "Net-(GPA3-3)") (class "Default")
      (node (ref "GPA3") (pin "1") (pinfunction "3_1") (pintype "passive"))
      (node (ref "IC2") (pin "24") (pinfunction "GPA3_24") (pintype "bidirectional"))
    )
    (net (code "67") (name "Net-(GPA4-3)") (class "Default")
      (node (ref "GPA4") (pin "1") (pinfunction "3_1") (pintype "passive"))
      (node (ref "IC2") (pin "25") (pinfunction "GPA4_25") (pintype "bidirectional"))
    )
    (net (code "68") (name "Net-(GPA5-3)") (class "Default")
      (node (ref "GPA5") (pin "1") (pinfunction "3_1") (pintype "passive"))
      (node (ref "IC2") (pin "26") (pinfunction "GPA5_26") (pintype "bidirectional"))
    )
    (net (code "69") (name "Net-(GPA6-3)") (class "Default")
      (node (ref "GPA6") (pin "1") (pinfunction "3_1") (pintype "passive"))
      (node (ref "IC2") (pin "27") (pinfunction "GPA6_27") (pintype "bidirectional"))
    )
    (net (code "70") (name "Net-(GPA7-3)") (class "Default")
      (node (ref "GPA7") (pin "1") (pinfunction "3_1") (pintype "passive"))
      (node (ref "IC2") (pin "28") (pinfunction "GPA7_28") (pintype "bidirectional"))
    )
    (net (code "71") (name "Net-(GPB0-3)") (class "Default")
      (node (ref "GPB0") (pin "1") (pinfunction "3_1") (pintype "passive"))
      (node (ref "IC2") (pin "1") (pinfunction "GPB0_1") (pintype "bidirectional"))
    )
    (net (code "72") (name "Net-(GPB1-3)") (class "Default")
      (node (ref "GPB1") (pin "1") (pinfunction "3_1") (pintype "passive"))
      (node (ref "IC2") (pin "2") (pinfunction "GPB1_2") (pintype "bidirectional"))
    )
    (net (code "73") (name "Net-(GPB2-3)") (class "Default")
      (node (ref "GPB2") (pin "1") (pinfunction "3_1") (pintype "passive"))
      (node (ref "IC2") (pin "3") (pinfunction "GPB2_3") (pintype "bidirectional"))
    )
    (net (code "74") (name "Net-(GPB3-3)") (class "Default")
      (node (ref "GPB3") (pin "1") (pinfunction "3_1") (pintype "passive"))
      (node (ref "IC2") (pin "4") (pinfunction "GPB3_4") (pintype "bidirectional"))
    )
    (net (code "75") (name "Net-(GPB4-3)") (class "Default")
      (node (ref "GPB4") (pin "1") (pinfunction "3_1") (pintype "passive"))
      (node (ref "IC2") (pin "5") (pinfunction "GPB4_5") (pintype "bidirectional"))
    )
    (net (code "76") (name "Net-(GPB5-3)") (class "Default")
      (node (ref "GPB5") (pin "1") (pinfunction "3_1") (pintype "passive"))
      (node (ref "IC2") (pin "6") (pinfunction "GPB5_6") (pintype "bidirectional"))
    )
    (net (code "77") (name "Net-(GPB6-3)") (class "Default")
      (node (ref "GPB6") (pin "1") (pinfunction "3_1") (pintype "passive"))
      (node (ref "IC2") (pin "7") (pinfunction "GPB6_7") (pintype "bidirectional"))
    )
    (net (code "78") (name "Net-(GPB7-3)") (class "Default")
      (node (ref "GPB7") (pin "1") (pinfunction "3_1") (pintype "passive"))
      (node (ref "IC2") (pin "8") (pinfunction "GPB7_8") (pintype "bidirectional"))
    )
    (net (code "79") (name "Net-(IC1A--IN)") (class "Default")
      (node (ref "C4") (pin "1") (pinfunction "1_1") (pintype "passive"))
      (node (ref "IC1") (pin "2") (pinfunction "-IN_2") (pintype "input"))
      (node (ref "R2") (pin "1") (pinfunction "1_1") (pintype "passive"))
      (node (ref "R5") (pin "2") (pinfunction "2_2") (pintype "passive"))
    )
    (net (code "80") (name "Net-(IC1A-OUT)") (class "Default")
      (node (ref "C4") (pin "2") (pinfunction "2_2") (pintype "passive"))
      (node (ref "IC1") (pin "1") (pinfunction "OUT_1") (pintype "output"))
      (node (ref "R16") (pin "1") (pinfunction "1_1") (pintype "passive"))
      (node (ref "R2") (pin "2") (pinfunction "2_2") (pintype "passive"))
    )
    (net (code "81") (name "Net-(IC1B--IN)") (class "Default")
      (node (ref "C5") (pin "1") (pinfunction "1_1") (pintype "passive"))
      (node (ref "IC1") (pin "6") (pinfunction "-IN_6") (pintype "input"))
      (node (ref "R1") (pin "1") (pinfunction "1_1") (pintype "passive"))
      (node (ref "R6") (pin "2") (pinfunction "2_2") (pintype "passive"))
    )
    (net (code "82") (name "Net-(IC1B-OUT)") (class "Default")
      (node (ref "C5") (pin "2") (pinfunction "2_2") (pintype "passive"))
      (node (ref "IC1") (pin "7") (pinfunction "OUT_7") (pintype "output"))
      (node (ref "R1") (pin "2") (pinfunction "2_2") (pintype "passive"))
      (node (ref "R14") (pin "1") (pinfunction "1_1") (pintype "passive"))
    )
    (net (code "83") (name "Net-(IC1C--IN)") (class "Default")
      (node (ref "C8") (pin "1") (pinfunction "1_1") (pintype "passive"))
      (node (ref "IC1") (pin "9") (pinfunction "-IN_9") (pintype "input"))
      (node (ref "R10") (pin "1") (pinfunction "1_1") (pintype "passive"))
      (node (ref "R3") (pin "2") (pinfunction "2_2") (pintype "passive"))
    )
    (net (code "84") (name "Net-(IC1C-OUT)") (class "Default")
      (node (ref "C8") (pin "2") (pinfunction "2_2") (pintype "passive"))
      (node (ref "IC1") (pin "8") (pinfunction "OUT_8") (pintype "output"))
      (node (ref "R10") (pin "2") (pinfunction "2_2") (pintype "passive"))
      (node (ref "R18") (pin "1") (pinfunction "1_1") (pintype "passive"))
    )
    (net (code "85") (name "Net-(IC1D--IN)") (class "Default")
      (node (ref "C9") (pin "1") (pinfunction "1_1") (pintype "passive"))
      (node (ref "IC1") (pin "13") (pinfunction "-IN_13") (pintype "input"))
      (node (ref "R4") (pin "2") (pinfunction "2_2") (pintype "passive"))
      (node (ref "R9") (pin "1") (pinfunction "1_1") (pintype "passive"))
    )
    (net (code "86") (name "Net-(IC1D-OUT)") (class "Default")
      (node (ref "C9") (pin "2") (pinfunction "2_2") (pintype "passive"))
      (node (ref "IC1") (pin "14") (pinfunction "OUT_14") (pintype "output"))
      (node (ref "R17") (pin "1") (pinfunction "1_1") (pintype "passive"))
      (node (ref "R9") (pin "2") (pinfunction "2_2") (pintype "passive"))
    )
    (net (code "87") (name "Net-(IC2-~{RESET})") (class "Default")
      (node (ref "IC2") (pin "18") (pinfunction "~{RESET}_18") (pintype "input"))
      (node (ref "R19") (pin "2") (pinfunction "2_2") (pintype "passive"))
    )
    (net (code "88") (name "Net-(IC3A--IN)") (class "Default")
      (node (ref "C7") (pin "1") (pinfunction "1_1") (pintype "passive"))
      (node (ref "IC3") (pin "2") (pinfunction "-IN_2") (pintype "input"))
      (node (ref "R11") (pin "2") (pinfunction "2_2") (pintype "passive"))
      (node (ref "R12") (pin "2") (pinfunction "2_2") (pintype "passive"))
      (node (ref "R13") (pin "2") (pinfunction "2_2") (pintype "passive"))
      (node (ref "R8") (pin "1") (pinfunction "1_1") (pintype "passive"))
    )
    (net (code "89") (name "Net-(IC3B--IN)") (class "Default")
      (node (ref "C10") (pin "1") (pinfunction "1_1") (pintype "passive"))
      (node (ref "IC3") (pin "6") (pinfunction "-IN_6") (pintype "input"))
      (node (ref "R15") (pin "1") (pinfunction "1_1") (pintype "passive"))
      (node (ref "R29") (pin "2") (pinfunction "2_2") (pintype "passive"))
      (node (ref "R62") (pin "2") (pinfunction "2_2") (pintype "passive"))
      (node (ref "R63") (pin "2") (pinfunction "2_2") (pintype "passive"))
    )
    (net (code "90") (name "Net-(IC3C--IN)") (class "Default")
      (node (ref "C11") (pin "1") (pinfunction "1_1") (pintype "passive"))
      (node (ref "IC3") (pin "9") (pinfunction "-IN_9") (pintype "input"))
      (node (ref "R64") (pin "1") (pinfunction "1_1") (pintype "passive"))
      (node (ref "R65") (pin "2") (pinfunction "2_2") (pintype "passive"))
      (node (ref "R66") (pin "2") (pinfunction "2_2") (pintype "passive"))
      (node (ref "R67") (pin "2") (pinfunction "2_2") (pintype "passive"))
    )
    (net (code "91") (name "Net-(IC3D--IN)") (class "Default")
      (node (ref "C14") (pin "1") (pinfunction "1_1") (pintype "passive"))
      (node (ref "IC3") (pin "13") (pinfunction "-IN_13") (pintype "input"))
      (node (ref "R68") (pin "1") (pinfunction "1_1") (pintype "passive"))
      (node (ref "R69") (pin "2") (pinfunction "2_2") (pintype "passive"))
      (node (ref "R70") (pin "2") (pinfunction "2_2") (pintype "passive"))
      (node (ref "R71") (pin "2") (pinfunction "2_2") (pintype "passive"))
    )
    (net (code "92") (name "Net-(IC4A--IN)") (class "Default")
      (node (ref "C16") (pin "1") (pinfunction "1_1") (pintype "passive"))
      (node (ref "IC4") (pin "2") (pinfunction "-IN_2") (pintype "input"))
      (node (ref "R21") (pin "1") (pinfunction "1_1") (pintype "passive"))
      (node (ref "R22") (pin "2") (pinfunction "2_2") (pintype "passive"))
      (node (ref "R23") (pin "2") (pinfunction "2_2") (pintype "passive"))
      (node (ref "R24") (pin "2") (pinfunction "2_2") (pintype "passive"))
    )
    (net (code "93") (name "Net-(IC4B--IN)") (class "Default")
      (node (ref "C17") (pin "1") (pinfunction "1_1") (pintype "passive"))
      (node (ref "IC4") (pin "6") (pinfunction "-IN_6") (pintype "input"))
      (node (ref "R25") (pin "1") (pinfunction "1_1") (pintype "passive"))
      (node (ref "R26") (pin "2") (pinfunction "2_2") (pintype "passive"))
      (node (ref "R27") (pin "2") (pinfunction "2_2") (pintype "passive"))
      (node (ref "R28") (pin "2") (pinfunction "2_2") (pintype "passive"))
    )
    (net (code "94") (name "Net-(IC4C--IN)") (class "Default")
      (node (ref "C20") (pin "1") (pinfunction "1_1") (pintype "passive"))
      (node (ref "IC4") (pin "9") (pinfunction "-IN_9") (pintype "input"))
      (node (ref "R30") (pin "1") (pinfunction "1_1") (pintype "passive"))
      (node (ref "R31") (pin "2") (pinfunction "2_2") (pintype "passive"))
      (node (ref "R32") (pin "2") (pinfunction "2_2") (pintype "passive"))
      (node (ref "R33") (pin "2") (pinfunction "2_2") (pintype "passive"))
    )
    (net (code "95") (name "Net-(IC4D--IN)") (class "Default")
      (node (ref "C21") (pin "1") (pinfunction "1_1") (pintype "passive"))
      (node (ref "IC4") (pin "13") (pinfunction "-IN_13") (pintype "input"))
      (node (ref "R34") (pin "1") (pinfunction "1_1") (pintype "passive"))
      (node (ref "R35") (pin "2") (pinfunction "2_2") (pintype "passive"))
      (node (ref "R36") (pin "2") (pinfunction "2_2") (pintype "passive"))
      (node (ref "R37") (pin "2") (pinfunction "2_2") (pintype "passive"))
    )
    (net (code "96") (name "Net-(IC7-VI)") (class "Default")
      (node (ref "C28") (pin "2") (pinfunction "2_2") (pintype "passive"))
      (node (ref "IC7") (pin "1") (pinfunction "VI_1") (pintype "input"))
      (node (ref "L1") (pin "2") (pinfunction "2_2") (pintype "passive"))
    )
    (net (code "97") (name "Net-(IC9-VIN)") (class "Default")
      (node (ref "C29") (pin "2") (pinfunction "2_2") (pintype "passive"))
      (node (ref "IC9") (pin "3") (pinfunction "VIN_3") (pintype "power_in"))
      (node (ref "L2") (pin "2") (pinfunction "2_2") (pintype "passive"))
    )
    (net (code "98") (name "unconnected-(IC2-~{CS}-Pad11)") (class "Default")
      (node (ref "IC2") (pin "11") (pinfunction "~{CS}_11") (pintype "input"))
    )
  )
)
